# acadam_2.net
KiCad netlist of a schematic drawn in EAGLE
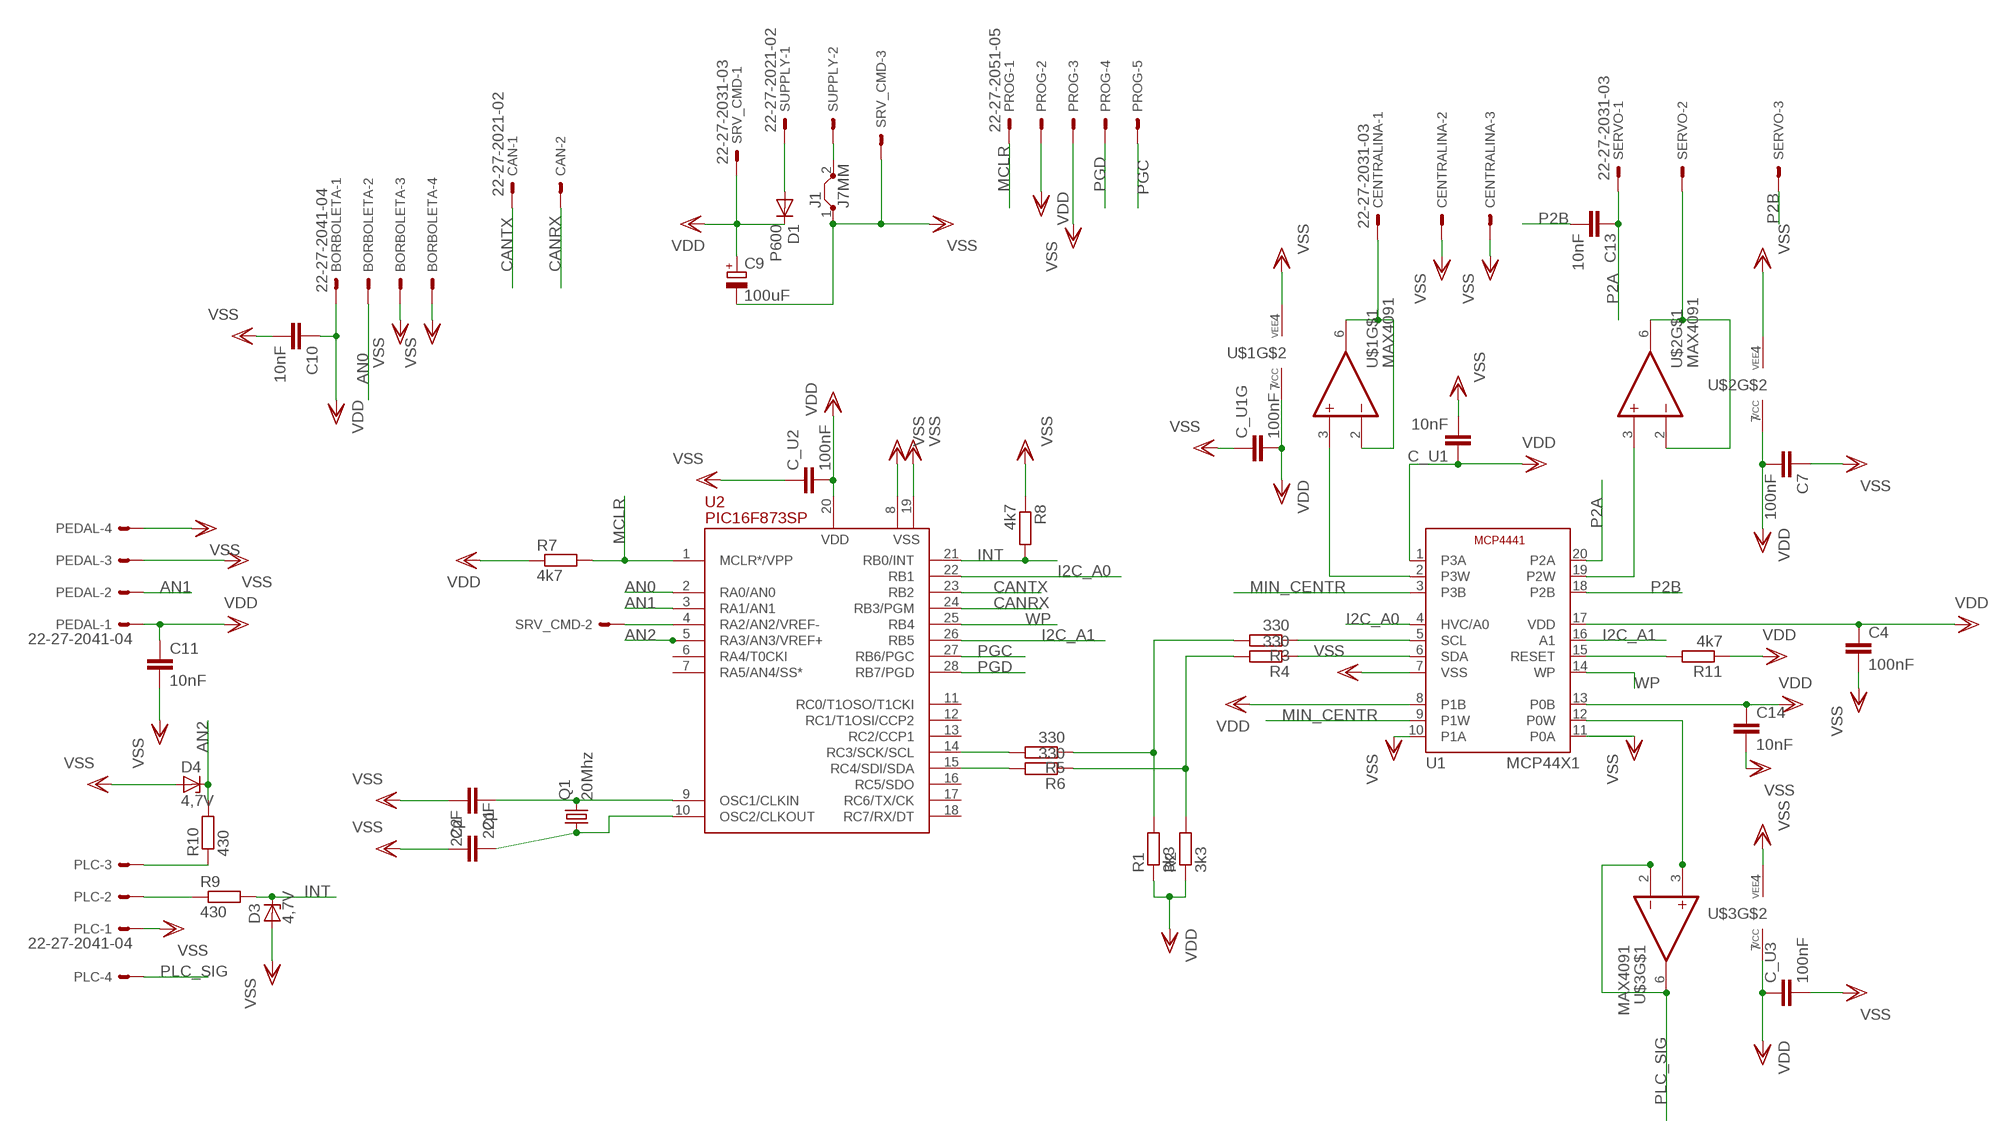
[diagram p0: schematic, sheet 1]

(export (version "E")
  (design (tool "Eeschema 10.0.6"))
  (components
    (comp (ref "BORBOLETA")
      (value "22-27-2041-04")
      (footprint "eagle-import:6410-04")
      (libsource (lib "eagle-import") (part "22-?-0427-2041"))
    )
    (comp (ref "C1")
      (value "22pF")
      (footprint "eagle-import:C0603")
      (libsource (lib "eagle-import") (part "C-EUC0603"))
    )
    (comp (ref "C2")
      (value "22pF")
      (footprint "eagle-import:C0603")
      (libsource (lib "eagle-import") (part "C-EUC0603"))
    )
    (comp (ref "C4")
      (value "100nF")
      (footprint "eagle-import:C0805")
      (libsource (lib "eagle-import") (part "C-EUC0805"))
    )
    (comp (ref "C7")
      (value "100nF")
      (footprint "eagle-import:C0805")
      (libsource (lib "eagle-import") (part "C-EUC0805"))
    )
    (comp (ref "C9")
      (value "100uF")
      (footprint "eagle-import:E2,5-5")
      (libsource (lib "eagle-import") (part "CPOL-EUE2.5-5"))
    )
    (comp (ref "C10")
      (value "10nF")
      (footprint "eagle-import:C0805")
      (libsource (lib "eagle-import") (part "C-EUC0805"))
    )
    (comp (ref "C11")
      (value "10nF")
      (footprint "eagle-import:C0805")
      (libsource (lib "eagle-import") (part "C-EUC0805"))
    )
    (comp (ref "C13")
      (value "10nF")
      (footprint "eagle-import:C0805")
      (libsource (lib "eagle-import") (part "C-EUC0805"))
    )
    (comp (ref "C14")
      (value "10nF")
      (footprint "eagle-import:C0805")
      (libsource (lib "eagle-import") (part "C-EUC0805"))
    )
    (comp (ref "CAN")
      (value "22-27-2021-02")
      (footprint "eagle-import:6410-02")
      (libsource (lib "eagle-import") (part "22-?-0227-2021"))
    )
    (comp (ref "CENTRALINA")
      (value "22-27-2031-03")
      (footprint "eagle-import:6410-03")
      (libsource (lib "eagle-import") (part "22-?-0327-2031"))
    )
    (comp (ref "C_U1")
      (value "10nF")
      (footprint "eagle-import:C0805")
      (libsource (lib "eagle-import") (part "C-EUC0805"))
    )
    (comp (ref "C_U1G")
      (value "100nF")
      (footprint "eagle-import:C0805")
      (libsource (lib "eagle-import") (part "C-EUC0805"))
    )
    (comp (ref "C_U2")
      (value "100nF")
      (footprint "eagle-import:C0805")
      (libsource (lib "eagle-import") (part "C-EUC0805"))
    )
    (comp (ref "C_U3")
      (value "100nF")
      (footprint "eagle-import:C0805")
      (libsource (lib "eagle-import") (part "C-EUC0805"))
    )
    (comp (ref "D1")
      (value "P600")
      (footprint "eagle-import:P6-15")
      (libsource (lib "eagle-import") (part "P600"))
    )
    (comp (ref "D3")
      (value "4,7V")
      (footprint "eagle-import:DO34Z7")
      (libsource (lib "eagle-import") (part "ZENER-DIODEDO34-7"))
    )
    (comp (ref "D4")
      (value "4,7V")
      (footprint "eagle-import:DO34Z7")
      (libsource (lib "eagle-import") (part "ZENER-DIODEDO34-7"))
    )
    (comp (ref "J1")
      (value "J7MM")
      (footprint "eagle-import:07")
      (libsource (lib "eagle-import") (part "J7MM"))
    )
    (comp (ref "PEDAL")
      (value "22-27-2041-04")
      (footprint "eagle-import:6410-04")
      (libsource (lib "eagle-import") (part "22-?-0427-2041"))
    )
    (comp (ref "PLC")
      (value "22-27-2041-04")
      (footprint "eagle-import:6410-04")
      (libsource (lib "eagle-import") (part "22-?-0427-2041"))
    )
    (comp (ref "PROG")
      (value "22-27-2051-05")
      (footprint "eagle-import:6410-05")
      (libsource (lib "eagle-import") (part "22-?-0527-2051"))
    )
    (comp (ref "Q1")
      (value "20Mhz")
      (footprint "eagle-import:HC49_S")
      (libsource (lib "eagle-import") (part "CRYSTALHC49S"))
    )
    (comp (ref "R1")
      (value "3k3")
      (footprint "eagle-import:0204_5")
      (libsource (lib "eagle-import") (part "R-EU_0204/5"))
    )
    (comp (ref "R2")
      (value "3k3")
      (footprint "eagle-import:0204_5")
      (libsource (lib "eagle-import") (part "R-EU_0204/5"))
    )
    (comp (ref "R3")
      (value "330")
      (footprint "eagle-import:0204_5")
      (libsource (lib "eagle-import") (part "R-EU_0204/5"))
    )
    (comp (ref "R4")
      (value "330")
      (footprint "eagle-import:0204_5")
      (libsource (lib "eagle-import") (part "R-EU_0204/5"))
    )
    (comp (ref "R5")
      (value "330")
      (footprint "eagle-import:0204_5")
      (libsource (lib "eagle-import") (part "R-EU_0204/5"))
    )
    (comp (ref "R6")
      (value "330")
      (footprint "eagle-import:0204_5")
      (libsource (lib "eagle-import") (part "R-EU_0204/5"))
    )
    (comp (ref "R7")
      (value "4k7")
      (footprint "eagle-import:0204_5")
      (libsource (lib "eagle-import") (part "R-EU_0204/5"))
    )
    (comp (ref "R8")
      (value "4k7")
      (footprint "eagle-import:0204_5")
      (libsource (lib "eagle-import") (part "R-EU_0204/5"))
    )
    (comp (ref "R9")
      (value "430")
      (footprint "eagle-import:0204_5")
      (libsource (lib "eagle-import") (part "R-EU_0204/5"))
    )
    (comp (ref "R10")
      (value "430")
      (footprint "eagle-import:0204_5")
      (libsource (lib "eagle-import") (part "R-EU_0204/5"))
    )
    (comp (ref "R11")
      (value "4k7")
      (footprint "eagle-import:0204_5")
      (libsource (lib "eagle-import") (part "R-EU_0204/5"))
    )
    (comp (ref "SERVO")
      (value "22-27-2031-03")
      (footprint "eagle-import:6410-03")
      (libsource (lib "eagle-import") (part "22-?-0327-2031"))
    )
    (comp (ref "SRV_CMD")
      (value "22-27-2031-03")
      (footprint "eagle-import:6410-03")
      (libsource (lib "eagle-import") (part "22-?-0327-2031"))
    )
    (comp (ref "SUPPLY")
      (value "22-27-2021-02")
      (footprint "eagle-import:6410-02")
      (libsource (lib "eagle-import") (part "22-?-0227-2021"))
    )
    (comp (ref "U$1")
      (value "MAX4091")
      (footprint "eagle-import:SO-08")
      (libsource (lib "eagle-import") (part "MAX4091"))
    )
    (comp (ref "U$2")
      (value "MAX4091")
      (footprint "eagle-import:SO-08")
      (libsource (lib "eagle-import") (part "MAX4091"))
    )
    (comp (ref "U$3")
      (value "MAX4091")
      (footprint "eagle-import:SO-08")
      (libsource (lib "eagle-import") (part "MAX4091"))
    )
    (comp (ref "U1")
      (value "MCP44X1")
      (footprint "eagle-import:TSSOP20")
      (libsource (lib "eagle-import") (part "MCP44X1"))
    )
    (comp (ref "U2")
      (value "PIC16F873SP")
      (footprint "eagle-import:DIL28-3")
      (libsource (lib "eagle-import") (part "PIC16F873SP"))
    )
  )
  (nets
    (net (code "1") (name "/AN0") (class "Default")
      (node (ref "BORBOLETA") (pin "2") (pinfunction "S_2") (pintype "passive"))
      (node (ref "U2") (pin "2") (pinfunction "RA0/AN0_2") (pintype "bidirectional"))
    )
    (net (code "2") (name "/AN1") (class "Default")
      (node (ref "PEDAL") (pin "2") (pinfunction "S_2") (pintype "passive"))
      (node (ref "U2") (pin "3") (pinfunction "RA1/AN1_3") (pintype "bidirectional"))
    )
    (net (code "3") (name "/AN2") (class "Default")
      (node (ref "D4") (pin "C") (pinfunction "C_C") (pintype "passive"))
      (node (ref "R10") (pin "2") (pinfunction "2_2") (pintype "passive"))
      (node (ref "U2") (pin "5") (pinfunction "RA3/AN3/VREF+_5") (pintype "bidirectional"))
    )
    (net (code "4") (name "/CANRX") (class "Default")
      (node (ref "CAN") (pin "2") (pinfunction "S_2") (pintype "passive"))
      (node (ref "U2") (pin "24") (pinfunction "RB3/PGM_24") (pintype "bidirectional"))
    )
    (net (code "5") (name "/CANTX") (class "Default")
      (node (ref "CAN") (pin "1") (pinfunction "S_1") (pintype "passive"))
      (node (ref "U2") (pin "23") (pinfunction "RB2_23") (pintype "bidirectional"))
    )
    (net (code "6") (name "/I2C_A0") (class "Default")
      (node (ref "U1") (pin "4") (pinfunction "HVC/A0_4") (pintype "bidirectional"))
      (node (ref "U2") (pin "22") (pinfunction "RB1_22") (pintype "bidirectional"))
    )
    (net (code "7") (name "/I2C_A1") (class "Default")
      (node (ref "U1") (pin "16") (pinfunction "A1_16") (pintype "bidirectional"))
      (node (ref "U2") (pin "26") (pinfunction "RB5_26") (pintype "bidirectional"))
    )
    (net (code "8") (name "/INT") (class "Default")
      (node (ref "D3") (pin "C") (pinfunction "C_C") (pintype "passive"))
      (node (ref "R8") (pin "2") (pinfunction "2_2") (pintype "passive"))
      (node (ref "R9") (pin "2") (pinfunction "2_2") (pintype "passive"))
      (node (ref "U2") (pin "21") (pinfunction "RB0/INT_21") (pintype "bidirectional"))
    )
    (net (code "9") (name "/MCLR") (class "Default")
      (node (ref "PROG") (pin "1") (pinfunction "S_1") (pintype "passive"))
      (node (ref "R7") (pin "2") (pinfunction "2_2") (pintype "passive"))
      (node (ref "U2") (pin "1") (pinfunction "MCLR*/VPP_1") (pintype "bidirectional"))
    )
    (net (code "10") (name "/MIN_CENTR") (class "Default")
      (node (ref "U1") (pin "3") (pinfunction "P3B_3") (pintype "bidirectional"))
      (node (ref "U1") (pin "9") (pinfunction "P1W_9") (pintype "bidirectional"))
    )
    (net (code "11") (name "/P2A") (class "Default")
      (node (ref "C13") (pin "1") (pinfunction "1_1") (pintype "passive"))
      (node (ref "SERVO") (pin "1") (pinfunction "S_1") (pintype "passive"))
      (node (ref "U1") (pin "20") (pinfunction "P2A_20") (pintype "bidirectional"))
    )
    (net (code "12") (name "/P2B") (class "Default")
      (node (ref "C13") (pin "2") (pinfunction "2_2") (pintype "passive"))
      (node (ref "SERVO") (pin "3") (pinfunction "S_3") (pintype "passive"))
      (node (ref "U1") (pin "18") (pinfunction "P2B_18") (pintype "bidirectional"))
    )
    (net (code "13") (name "/PGC") (class "Default")
      (node (ref "PROG") (pin "5") (pinfunction "S_5") (pintype "passive"))
      (node (ref "U2") (pin "27") (pinfunction "RB6/PGC_27") (pintype "bidirectional"))
    )
    (net (code "14") (name "/PGD") (class "Default")
      (node (ref "PROG") (pin "4") (pinfunction "S_4") (pintype "passive"))
      (node (ref "U2") (pin "28") (pinfunction "RB7/PGD_28") (pintype "bidirectional"))
    )
    (net (code "15") (name "/PLC_SIG") (class "Default")
      (node (ref "PLC") (pin "4") (pinfunction "S_4") (pintype "passive"))
      (node (ref "U$3") (pin "2") (pinfunction "-IN_2") (pintype "input"))
      (node (ref "U$3") (pin "6") (pinfunction "OUT_6") (pintype "output"))
    )
    (net (code "16") (name "/WP") (class "Default")
      (node (ref "U1") (pin "14") (pinfunction "WP_14") (pintype "bidirectional"))
      (node (ref "U2") (pin "25") (pinfunction "RB4_25") (pintype "bidirectional"))
    )
    (net (code "17") (name "Net-(CENTRALINAA-S)") (class "Default")
      (node (ref "CENTRALINA") (pin "1") (pinfunction "S_1") (pintype "passive"))
      (node (ref "U$1") (pin "2") (pinfunction "-IN_2") (pintype "input"))
      (node (ref "U$1") (pin "6") (pinfunction "OUT_6") (pintype "output"))
    )
    (net (code "18") (name "Net-(PLCB-S)") (class "Default")
      (node (ref "PLC") (pin "2") (pinfunction "S_2") (pintype "passive"))
      (node (ref "R9") (pin "1") (pinfunction "1_1") (pintype "passive"))
    )
    (net (code "19") (name "Net-(PLCC-S)") (class "Default")
      (node (ref "PLC") (pin "3") (pinfunction "S_3") (pintype "passive"))
      (node (ref "R10") (pin "1") (pinfunction "1_1") (pintype "passive"))
    )
    (net (code "20") (name "Net-(R1-Pad2)") (class "Default")
      (node (ref "R1") (pin "2") (pinfunction "2_2") (pintype "passive"))
      (node (ref "R3") (pin "2") (pinfunction "2_2") (pintype "passive"))
      (node (ref "R5") (pin "1") (pinfunction "1_1") (pintype "passive"))
    )
    (net (code "21") (name "Net-(R2-Pad2)") (class "Default")
      (node (ref "R2") (pin "2") (pinfunction "2_2") (pintype "passive"))
      (node (ref "R4") (pin "2") (pinfunction "2_2") (pintype "passive"))
      (node (ref "R6") (pin "1") (pinfunction "1_1") (pintype "passive"))
    )
    (net (code "22") (name "Net-(SERVOB-S)") (class "Default")
      (node (ref "SERVO") (pin "2") (pinfunction "S_2") (pintype "passive"))
      (node (ref "U$2") (pin "2") (pinfunction "-IN_2") (pintype "input"))
      (node (ref "U$2") (pin "6") (pinfunction "OUT_6") (pintype "output"))
    )
    (net (code "23") (name "Net-(SRV_CMDB-S)") (class "Default")
      (node (ref "SRV_CMD") (pin "2") (pinfunction "S_2") (pintype "passive"))
      (node (ref "U2") (pin "4") (pinfunction "RA2/AN2/VREF-_4") (pintype "bidirectional"))
    )
    (net (code "24") (name "Net-(SUPPLYA-S)") (class "Default")
      (node (ref "D1") (pin "A") (pinfunction "A_A") (pintype "passive"))
      (node (ref "SUPPLY") (pin "1") (pinfunction "S_1") (pintype "passive"))
    )
    (net (code "25") (name "Net-(SUPPLYB-S)") (class "Default")
      (node (ref "J1") (pin "2") (pinfunction "2_2") (pintype "passive"))
      (node (ref "SUPPLY") (pin "2") (pinfunction "S_2") (pintype "passive"))
    )
    (net (code "26") (name "Net-(U$1A-+IN)") (class "Default")
      (node (ref "U$1") (pin "3") (pinfunction "+IN_3") (pintype "input"))
      (node (ref "U1") (pin "2") (pinfunction "P3W_2") (pintype "bidirectional"))
    )
    (net (code "27") (name "Net-(U$2A-+IN)") (class "Default")
      (node (ref "U$2") (pin "3") (pinfunction "+IN_3") (pintype "input"))
      (node (ref "U1") (pin "19") (pinfunction "P2W_19") (pintype "bidirectional"))
    )
    (net (code "28") (name "Net-(U$3A-+IN)") (class "Default")
      (node (ref "U$3") (pin "3") (pinfunction "+IN_3") (pintype "input"))
      (node (ref "U1") (pin "12") (pinfunction "P0W_12") (pintype "bidirectional"))
    )
    (net (code "29") (name "Net-(U1-RESET)") (class "Default")
      (node (ref "R11") (pin "2") (pinfunction "2_2") (pintype "passive"))
      (node (ref "U1") (pin "15") (pinfunction "RESET_15") (pintype "bidirectional"))
    )
    (net (code "30") (name "Net-(U1-SCL)") (class "Default")
      (node (ref "R3") (pin "1") (pinfunction "1_1") (pintype "passive"))
      (node (ref "U1") (pin "5") (pinfunction "SCL_5") (pintype "bidirectional"))
    )
    (net (code "31") (name "Net-(U1-SDA)") (class "Default")
      (node (ref "R4") (pin "1") (pinfunction "1_1") (pintype "passive"))
      (node (ref "U1") (pin "6") (pinfunction "SDA_6") (pintype "bidirectional"))
    )
    (net (code "32") (name "Net-(U2-OSC1{slash}CLKIN)") (class "Default")
      (node (ref "C1") (pin "1") (pinfunction "1_1") (pintype "passive"))
      (node (ref "Q1") (pin "2") (pinfunction "2_2") (pintype "passive"))
      (node (ref "U2") (pin "9") (pinfunction "OSC1/CLKIN_9") (pintype "bidirectional"))
    )
    (net (code "33") (name "Net-(U2-OSC2{slash}CLKOUT)") (class "Default")
      (node (ref "C2") (pin "2") (pinfunction "2_2") (pintype "passive"))
      (node (ref "Q1") (pin "1") (pinfunction "1_1") (pintype "passive"))
      (node (ref "U2") (pin "10") (pinfunction "OSC2/CLKOUT_10") (pintype "bidirectional"))
    )
    (net (code "34") (name "Net-(U2-RC3{slash}SCK{slash}SCL)") (class "Default")
      (node (ref "R5") (pin "2") (pinfunction "2_2") (pintype "passive"))
      (node (ref "U2") (pin "14") (pinfunction "RC3/SCK/SCL_14") (pintype "bidirectional"))
    )
    (net (code "35") (name "Net-(U2-RC4{slash}SDI{slash}SDA)") (class "Default")
      (node (ref "R6") (pin "2") (pinfunction "2_2") (pintype "passive"))
      (node (ref "U2") (pin "15") (pinfunction "RC4/SDI/SDA_15") (pintype "bidirectional"))
    )
    (net (code "36") (name "VDD") (class "Default")
      (node (ref "BORBOLETA") (pin "1") (pinfunction "S_1") (pintype "passive"))
      (node (ref "C10") (pin "1") (pinfunction "1_1") (pintype "passive"))
      (node (ref "C11") (pin "1") (pinfunction "1_1") (pintype "passive"))
      (node (ref "C14") (pin "1") (pinfunction "1_1") (pintype "passive"))
      (node (ref "C4") (pin "1") (pinfunction "1_1") (pintype "passive"))
      (node (ref "C7") (pin "2") (pinfunction "2_2") (pintype "passive"))
      (node (ref "C9") (pin "+") (pinfunction "+_+") (pintype "passive"))
      (node (ref "C_U1") (pin "1") (pinfunction "1_1") (pintype "passive"))
      (node (ref "C_U1G") (pin "2") (pinfunction "2_2") (pintype "passive"))
      (node (ref "C_U2") (pin "2") (pinfunction "2_2") (pintype "passive"))
      (node (ref "C_U3") (pin "1") (pinfunction "1_1") (pintype "passive"))
      (node (ref "D1") (pin "C") (pinfunction "C_C") (pintype "passive"))
      (node (ref "PEDAL") (pin "1") (pinfunction "S_1") (pintype "passive"))
      (node (ref "PROG") (pin "2") (pinfunction "S_2") (pintype "passive"))
      (node (ref "R1") (pin "1") (pinfunction "1_1") (pintype "passive"))
      (node (ref "R11") (pin "1") (pinfunction "1_1") (pintype "passive"))
      (node (ref "R2") (pin "1") (pinfunction "1_1") (pintype "passive"))
      (node (ref "R7") (pin "1") (pinfunction "1_1") (pintype "passive"))
      (node (ref "SRV_CMD") (pin "1") (pinfunction "S_1") (pintype "passive"))
      (node (ref "U$1") (pin "7") (pinfunction "VCC_7") (pintype "power_in"))
      (node (ref "U$2") (pin "7") (pinfunction "VCC_7") (pintype "power_in"))
      (node (ref "U$3") (pin "7") (pinfunction "VCC_7") (pintype "power_in"))
      (node (ref "U1") (pin "1") (pinfunction "P3A_1") (pintype "bidirectional"))
      (node (ref "U1") (pin "13") (pinfunction "P0B_13") (pintype "bidirectional"))
      (node (ref "U1") (pin "17") (pinfunction "VDD_17") (pintype "bidirectional"))
      (node (ref "U1") (pin "8") (pinfunction "P1B_8") (pintype "bidirectional"))
      (node (ref "U2") (pin "20") (pinfunction "VDD_20") (pintype "power_in"))
    )
    (net (code "37") (name "VSS") (class "Default")
      (node (ref "BORBOLETA") (pin "3") (pinfunction "S_3") (pintype "passive"))
      (node (ref "BORBOLETA") (pin "4") (pinfunction "S_4") (pintype "passive"))
      (node (ref "C1") (pin "2") (pinfunction "2_2") (pintype "passive"))
      (node (ref "C10") (pin "2") (pinfunction "2_2") (pintype "passive"))
      (node (ref "C11") (pin "2") (pinfunction "2_2") (pintype "passive"))
      (node (ref "C14") (pin "2") (pinfunction "2_2") (pintype "passive"))
      (node (ref "C2") (pin "1") (pinfunction "1_1") (pintype "passive"))
      (node (ref "C4") (pin "2") (pinfunction "2_2") (pintype "passive"))
      (node (ref "C7") (pin "1") (pinfunction "1_1") (pintype "passive"))
      (node (ref "C9") (pin "-") (pinfunction "-_-") (pintype "passive"))
      (node (ref "CENTRALINA") (pin "2") (pinfunction "S_2") (pintype "passive"))
      (node (ref "CENTRALINA") (pin "3") (pinfunction "S_3") (pintype "passive"))
      (node (ref "C_U1") (pin "2") (pinfunction "2_2") (pintype "passive"))
      (node (ref "C_U1G") (pin "1") (pinfunction "1_1") (pintype "passive"))
      (node (ref "C_U2") (pin "1") (pinfunction "1_1") (pintype "passive"))
      (node (ref "C_U3") (pin "2") (pinfunction "2_2") (pintype "passive"))
      (node (ref "D3") (pin "A") (pinfunction "A_A") (pintype "passive"))
      (node (ref "D4") (pin "A") (pinfunction "A_A") (pintype "passive"))
      (node (ref "J1") (pin "1") (pinfunction "1_1") (pintype "passive"))
      (node (ref "PEDAL") (pin "3") (pinfunction "S_3") (pintype "passive"))
      (node (ref "PEDAL") (pin "4") (pinfunction "S_4") (pintype "passive"))
      (node (ref "PLC") (pin "1") (pinfunction "S_1") (pintype "passive"))
      (node (ref "PROG") (pin "3") (pinfunction "S_3") (pintype "passive"))
      (node (ref "R8") (pin "1") (pinfunction "1_1") (pintype "passive"))
      (node (ref "SRV_CMD") (pin "3") (pinfunction "S_3") (pintype "passive"))
      (node (ref "U$1") (pin "4") (pinfunction "VEE_4") (pintype "power_in"))
      (node (ref "U$2") (pin "4") (pinfunction "VEE_4") (pintype "power_in"))
      (node (ref "U$3") (pin "4") (pinfunction "VEE_4") (pintype "power_in"))
      (node (ref "U1") (pin "10") (pinfunction "P1A_10") (pintype "bidirectional"))
      (node (ref "U1") (pin "11") (pinfunction "P0A_11") (pintype "bidirectional"))
      (node (ref "U1") (pin "7") (pinfunction "VSS_7") (pintype "bidirectional"))
      (node (ref "U2") (pin "19") (pinfunction "VSS_19") (pintype "power_in"))
      (node (ref "U2") (pin "8") (pinfunction "VSS_8") (pintype "power_in"))
    )
    (net (code "38") (name "unconnected-(U2-RA4{slash}T0CKI-Pad6)") (class "Default")
      (node (ref "U2") (pin "6") (pinfunction "RA4/T0CKI_6") (pintype "bidirectional"))
    )
    (net (code "39") (name "unconnected-(U2-RA5{slash}AN4{slash}SS*-Pad7)") (class "Default")
      (node (ref "U2") (pin "7") (pinfunction "RA5/AN4/SS*_7") (pintype "bidirectional"))
    )
    (net (code "40") (name "unconnected-(U2-RC0{slash}T1OSO{slash}T1CKI-Pad11)") (class "Default")
      (node (ref "U2") (pin "11") (pinfunction "RC0/T1OSO/T1CKI_11") (pintype "bidirectional"))
    )
    (net (code "41") (name "unconnected-(U2-RC1{slash}T1OSI{slash}CCP2-Pad12)") (class "Default")
      (node (ref "U2") (pin "12") (pinfunction "RC1/T1OSI/CCP2_12") (pintype "bidirectional"))
    )
    (net (code "42") (name "unconnected-(U2-RC2{slash}CCP1-Pad13)") (class "Default")
      (node (ref "U2") (pin "13") (pinfunction "RC2/CCP1_13") (pintype "bidirectional"))
    )
    (net (code "43") (name "unconnected-(U2-RC5{slash}SDO-Pad16)") (class "Default")
      (node (ref "U2") (pin "16") (pinfunction "RC5/SDO_16") (pintype "bidirectional"))
    )
    (net (code "44") (name "unconnected-(U2-RC6{slash}TX{slash}CK-Pad17)") (class "Default")
      (node (ref "U2") (pin "17") (pinfunction "RC6/TX/CK_17") (pintype "bidirectional"))
    )
    (net (code "45") (name "unconnected-(U2-RC7{slash}RX{slash}DT-Pad18)") (class "Default")
      (node (ref "U2") (pin "18") (pinfunction "RC7/RX/DT_18") (pintype "bidirectional"))
    )
  )
)
